# Analog.net
KiCad netlist of a schematic drawn in Altium Designer
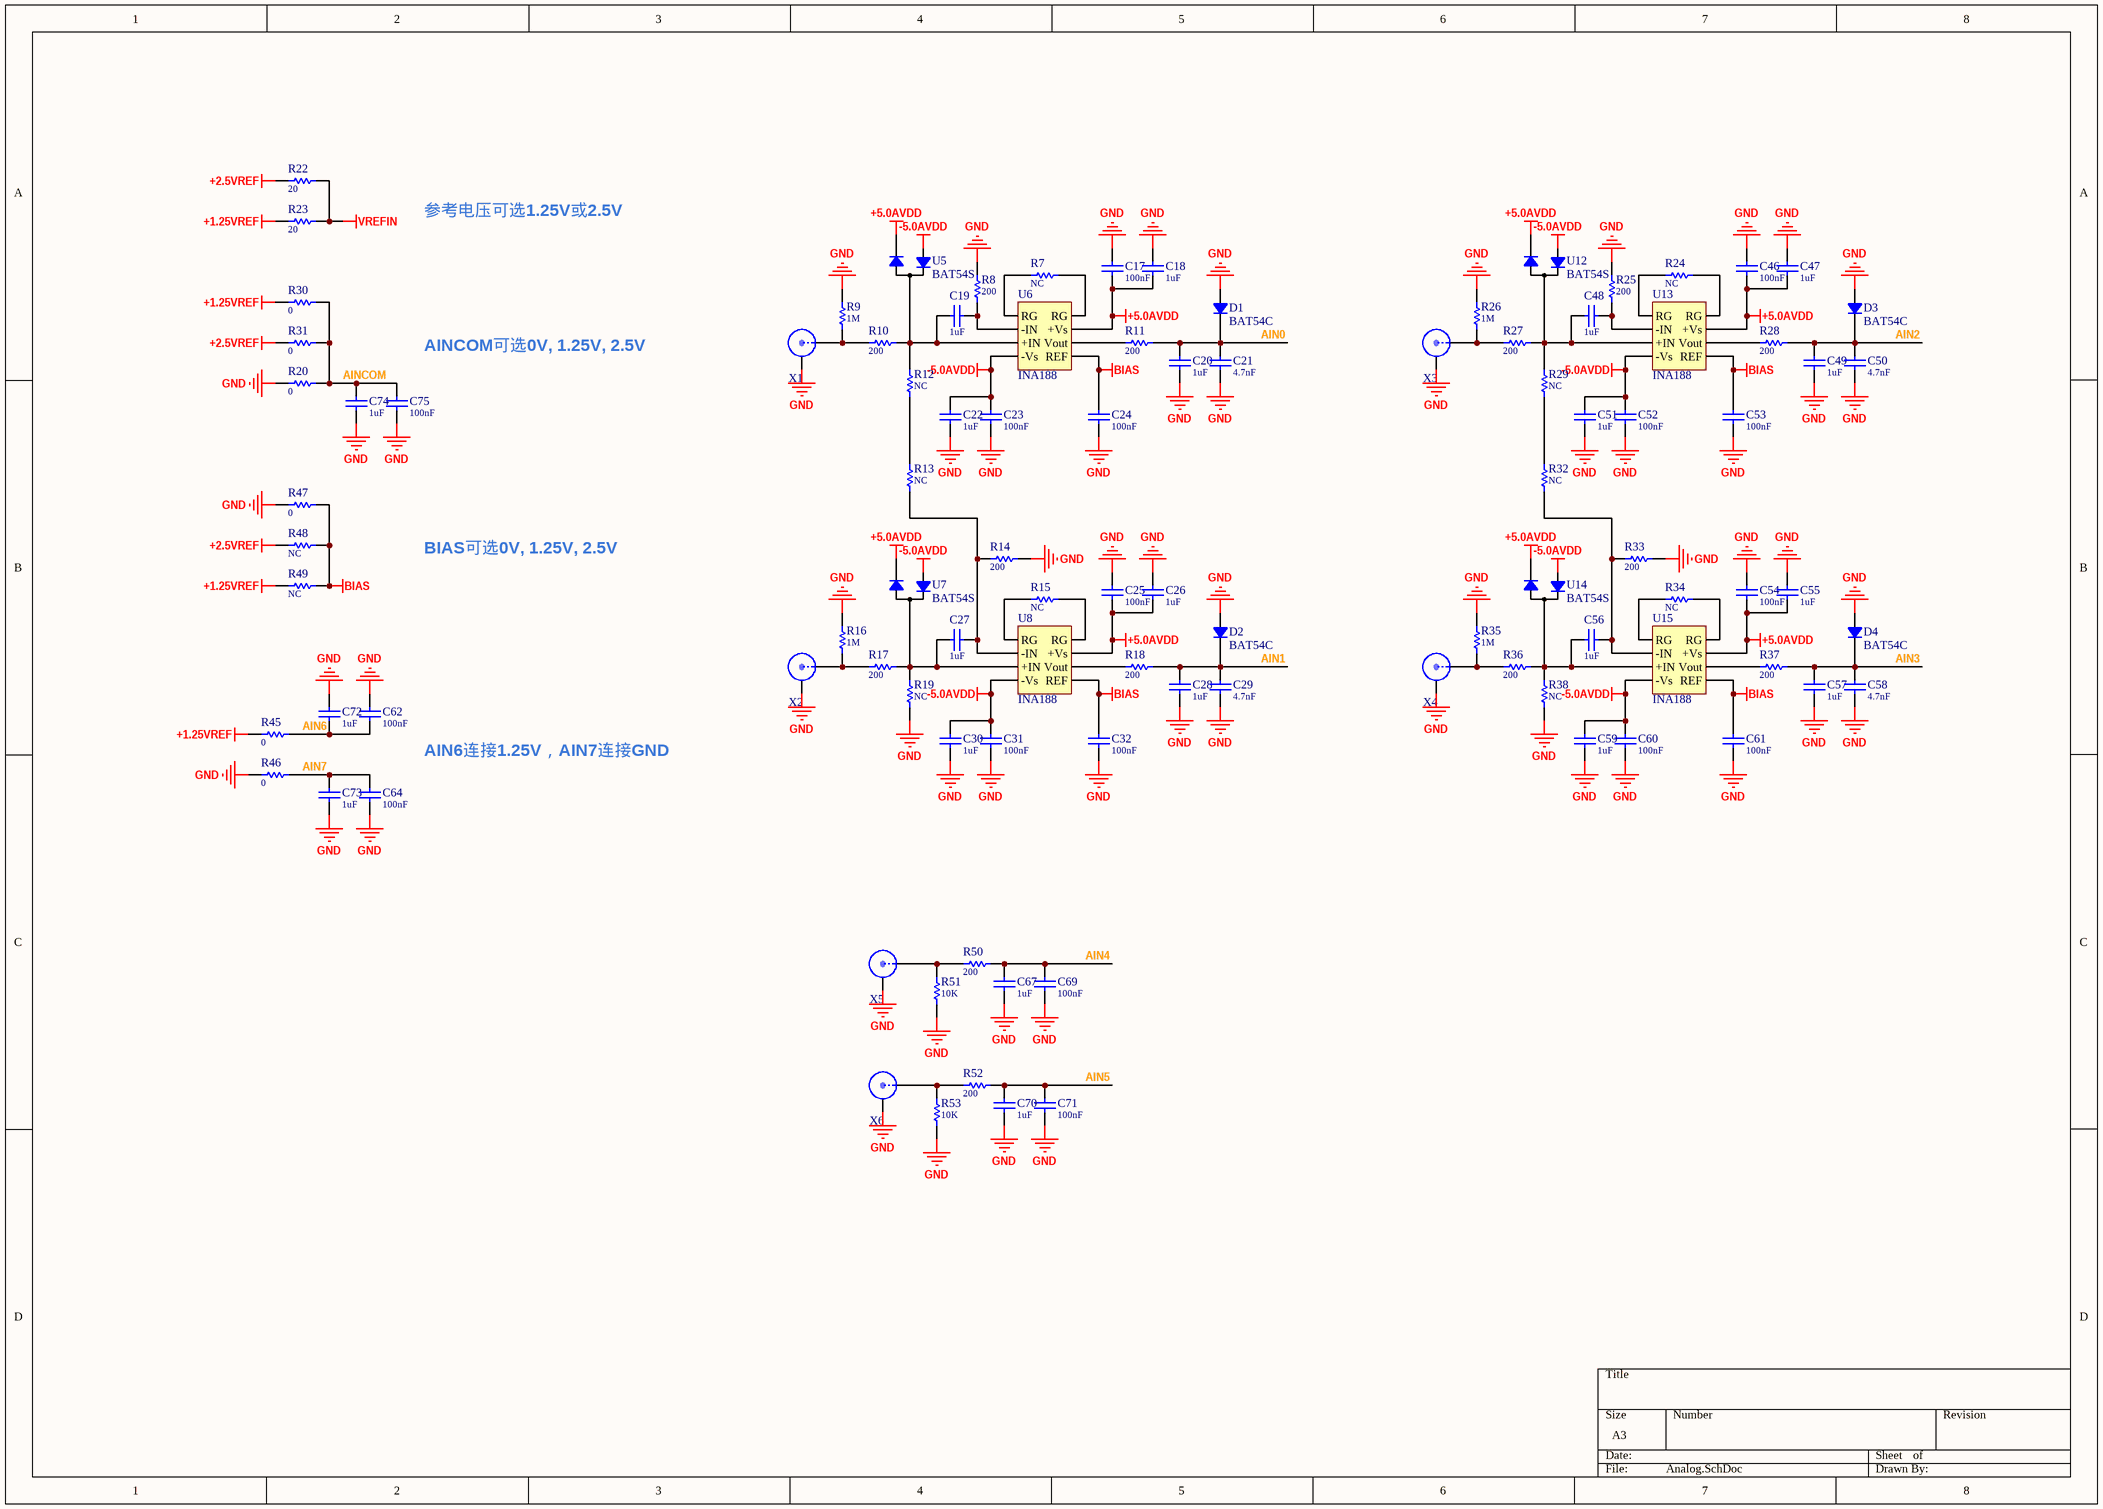
[diagram p0: Analog.SchDoc]

(export (version "E")
  (design (tool "Eeschema 10.0.6"))
  (components
    (comp (ref "C17")
      (value "100nF")
      (footprint "C0402-L")
      (description "贴片瓷片电容")
      (fields (field (name "Comment") "Cap-S"))
      (libsource (lib "xz_D") (part "Cap-S"))
    )
    (comp (ref "C18")
      (value "1uF")
      (footprint "C0603-L")
      (description "贴片瓷片电容")
      (fields (field (name "Comment") "Cap-S"))
      (libsource (lib "xz_D") (part "Cap-S"))
    )
    (comp (ref "C19")
      (value "1uF")
      (footprint "C0603-L")
      (description "贴片瓷片电容")
      (fields (field (name "Comment") "Cap-S"))
      (libsource (lib "xz_D") (part "Cap-S"))
    )
    (comp (ref "C20")
      (value "1uF")
      (footprint "C0603-L")
      (description "贴片瓷片电容")
      (fields (field (name "Comment") "Cap-S"))
      (libsource (lib "xz_D") (part "Cap-S"))
    )
    (comp (ref "C21")
      (value "4.7nF")
      (footprint "C0402-L")
      (description "贴片瓷片电容")
      (fields (field (name "Comment") "Cap-S"))
      (libsource (lib "xz_D") (part "Cap-S"))
    )
    (comp (ref "C22")
      (value "1uF")
      (footprint "C0603-L")
      (description "贴片瓷片电容")
      (fields (field (name "Comment") "Cap-S"))
      (libsource (lib "xz_D") (part "Cap-S"))
    )
    (comp (ref "C23")
      (value "100nF")
      (footprint "C0402-L")
      (description "贴片瓷片电容")
      (fields (field (name "Comment") "Cap-S"))
      (libsource (lib "xz_D") (part "Cap-S"))
    )
    (comp (ref "C24")
      (value "100nF")
      (footprint "C0402-L")
      (description "贴片瓷片电容")
      (fields (field (name "Comment") "Cap-S"))
      (libsource (lib "xz_D") (part "Cap-S"))
    )
    (comp (ref "C25")
      (value "100nF")
      (footprint "C0402-L")
      (description "贴片瓷片电容")
      (fields (field (name "Comment") "Cap-S"))
      (libsource (lib "xz_D") (part "Cap-S"))
    )
    (comp (ref "C26")
      (value "1uF")
      (footprint "C0603-L")
      (description "贴片瓷片电容")
      (fields (field (name "Comment") "Cap-S"))
      (libsource (lib "xz_D") (part "Cap-S"))
    )
    (comp (ref "C27")
      (value "1uF")
      (footprint "C0603-L")
      (description "贴片瓷片电容")
      (fields (field (name "Comment") "Cap-S"))
      (libsource (lib "xz_D") (part "Cap-S"))
    )
    (comp (ref "C28")
      (value "1uF")
      (footprint "C0603-L")
      (description "贴片瓷片电容")
      (fields (field (name "Comment") "Cap-S"))
      (libsource (lib "xz_D") (part "Cap-S"))
    )
    (comp (ref "C29")
      (value "4.7nF")
      (footprint "C0402-L")
      (description "贴片瓷片电容")
      (fields (field (name "Comment") "Cap-S"))
      (libsource (lib "xz_D") (part "Cap-S"))
    )
    (comp (ref "C30")
      (value "1uF")
      (footprint "C0603-L")
      (description "贴片瓷片电容")
      (fields (field (name "Comment") "Cap-S"))
      (libsource (lib "xz_D") (part "Cap-S"))
    )
    (comp (ref "C31")
      (value "100nF")
      (footprint "C0402-L")
      (description "贴片瓷片电容")
      (fields (field (name "Comment") "Cap-S"))
      (libsource (lib "xz_D") (part "Cap-S"))
    )
    (comp (ref "C32")
      (value "100nF")
      (footprint "C0402-L")
      (description "贴片瓷片电容")
      (fields (field (name "Comment") "Cap-S"))
      (libsource (lib "xz_D") (part "Cap-S"))
    )
    (comp (ref "C46")
      (value "100nF")
      (footprint "C0402-L")
      (description "贴片瓷片电容")
      (fields (field (name "Comment") "Cap-S"))
      (libsource (lib "xz_D") (part "Cap-S"))
    )
    (comp (ref "C47")
      (value "1uF")
      (footprint "C0603-L")
      (description "贴片瓷片电容")
      (fields (field (name "Comment") "Cap-S"))
      (libsource (lib "xz_D") (part "Cap-S"))
    )
    (comp (ref "C48")
      (value "1uF")
      (footprint "C0603-L")
      (description "贴片瓷片电容")
      (fields (field (name "Comment") "Cap-S"))
      (libsource (lib "xz_D") (part "Cap-S"))
    )
    (comp (ref "C49")
      (value "1uF")
      (footprint "C0603-L")
      (description "贴片瓷片电容")
      (fields (field (name "Comment") "Cap-S"))
      (libsource (lib "xz_D") (part "Cap-S"))
    )
    (comp (ref "C50")
      (value "4.7nF")
      (footprint "C0402-L")
      (description "贴片瓷片电容")
      (fields (field (name "Comment") "Cap-S"))
      (libsource (lib "xz_D") (part "Cap-S"))
    )
    (comp (ref "C51")
      (value "1uF")
      (footprint "C0603-L")
      (description "贴片瓷片电容")
      (fields (field (name "Comment") "Cap-S"))
      (libsource (lib "xz_D") (part "Cap-S"))
    )
    (comp (ref "C52")
      (value "100nF")
      (footprint "C0402-L")
      (description "贴片瓷片电容")
      (fields (field (name "Comment") "Cap-S"))
      (libsource (lib "xz_D") (part "Cap-S"))
    )
    (comp (ref "C53")
      (value "100nF")
      (footprint "C0402-L")
      (description "贴片瓷片电容")
      (fields (field (name "Comment") "Cap-S"))
      (libsource (lib "xz_D") (part "Cap-S"))
    )
    (comp (ref "C54")
      (value "100nF")
      (footprint "C0402-L")
      (description "贴片瓷片电容")
      (fields (field (name "Comment") "Cap-S"))
      (libsource (lib "xz_D") (part "Cap-S"))
    )
    (comp (ref "C55")
      (value "1uF")
      (footprint "C0603-L")
      (description "贴片瓷片电容")
      (fields (field (name "Comment") "Cap-S"))
      (libsource (lib "xz_D") (part "Cap-S"))
    )
    (comp (ref "C56")
      (value "1uF")
      (footprint "C0603-L")
      (description "贴片瓷片电容")
      (fields (field (name "Comment") "Cap-S"))
      (libsource (lib "xz_D") (part "Cap-S"))
    )
    (comp (ref "C57")
      (value "1uF")
      (footprint "C0603-L")
      (description "贴片瓷片电容")
      (fields (field (name "Comment") "Cap-S"))
      (libsource (lib "xz_D") (part "Cap-S"))
    )
    (comp (ref "C58")
      (value "4.7nF")
      (footprint "C0402-L")
      (description "贴片瓷片电容")
      (fields (field (name "Comment") "Cap-S"))
      (libsource (lib "xz_D") (part "Cap-S"))
    )
    (comp (ref "C59")
      (value "1uF")
      (footprint "C0603-L")
      (description "贴片瓷片电容")
      (fields (field (name "Comment") "Cap-S"))
      (libsource (lib "xz_D") (part "Cap-S"))
    )
    (comp (ref "C60")
      (value "100nF")
      (footprint "C0402-L")
      (description "贴片瓷片电容")
      (fields (field (name "Comment") "Cap-S"))
      (libsource (lib "xz_D") (part "Cap-S"))
    )
    (comp (ref "C61")
      (value "100nF")
      (footprint "C0402-L")
      (description "贴片瓷片电容")
      (fields (field (name "Comment") "Cap-S"))
      (libsource (lib "xz_D") (part "Cap-S"))
    )
    (comp (ref "C62")
      (value "100nF")
      (footprint "C0402-L")
      (description "贴片瓷片电容")
      (fields (field (name "Comment") "Cap-S"))
      (libsource (lib "xz_D") (part "Cap-S"))
    )
    (comp (ref "C64")
      (value "100nF")
      (footprint "C0402-L")
      (description "贴片瓷片电容")
      (fields (field (name "Comment") "Cap-S"))
      (libsource (lib "xz_D") (part "Cap-S"))
    )
    (comp (ref "C67")
      (value "1uF")
      (footprint "C0603-L")
      (description "贴片瓷片电容")
      (fields (field (name "Comment") "Cap-S"))
      (libsource (lib "xz_D") (part "Cap-S"))
    )
    (comp (ref "C69")
      (value "100nF")
      (footprint "C0402-L")
      (description "贴片瓷片电容")
      (fields (field (name "Comment") "Cap-S"))
      (libsource (lib "xz_D") (part "Cap-S"))
    )
    (comp (ref "C70")
      (value "1uF")
      (footprint "C0603-L")
      (description "贴片瓷片电容")
      (fields (field (name "Comment") "Cap-S"))
      (libsource (lib "xz_D") (part "Cap-S"))
    )
    (comp (ref "C71")
      (value "100nF")
      (footprint "C0402-L")
      (description "贴片瓷片电容")
      (fields (field (name "Comment") "Cap-S"))
      (libsource (lib "xz_D") (part "Cap-S"))
    )
    (comp (ref "C72")
      (value "1uF")
      (footprint "C0603-L")
      (description "贴片瓷片电容")
      (fields (field (name "Comment") "Cap-S"))
      (libsource (lib "xz_D") (part "Cap-S"))
    )
    (comp (ref "C73")
      (value "1uF")
      (footprint "C0603-L")
      (description "贴片瓷片电容")
      (fields (field (name "Comment") "Cap-S"))
      (libsource (lib "xz_D") (part "Cap-S"))
    )
    (comp (ref "C74")
      (value "1uF")
      (footprint "C0603-L")
      (description "贴片瓷片电容")
      (fields (field (name "Comment") "Cap-S"))
      (libsource (lib "xz_D") (part "Cap-S"))
    )
    (comp (ref "C75")
      (value "100nF")
      (footprint "C0402-L")
      (description "贴片瓷片电容")
      (fields (field (name "Comment") "Cap-S"))
      (libsource (lib "xz_D") (part "Cap-S"))
    )
    (comp (ref "D1") (value "BAT54C") (footprint "SOT-23-2") (libsource (lib "CommonUsed") (part "BAT54C")))
    (comp (ref "D2") (value "BAT54C") (footprint "SOT-23-2") (libsource (lib "CommonUsed") (part "BAT54C")))
    (comp (ref "D3") (value "BAT54C") (footprint "SOT-23-2") (libsource (lib "CommonUsed") (part "BAT54C")))
    (comp (ref "D4") (value "BAT54C") (footprint "SOT-23-2") (libsource (lib "CommonUsed") (part "BAT54C")))
    (comp (ref "R7")
      (value "NC")
      (footprint "R0603-L")
      (description "贴片电阻")
      (fields (field (name "Comment") "R"))
      (libsource (lib "xz_D") (part "Res"))
    )
    (comp (ref "R8")
      (value "200")
      (footprint "R0603-L")
      (description "贴片电阻")
      (fields (field (name "Comment") "R"))
      (libsource (lib "xz_D") (part "Res"))
    )
    (comp (ref "R9")
      (value "1M")
      (footprint "R0603-L")
      (description "贴片电阻")
      (fields (field (name "Comment") "R"))
      (libsource (lib "xz_D") (part "Res"))
    )
    (comp (ref "R10")
      (value "200")
      (footprint "R0603-L")
      (description "贴片电阻")
      (fields (field (name "Comment") "R"))
      (libsource (lib "xz_D") (part "Res"))
    )
    (comp (ref "R11")
      (value "200")
      (footprint "R0603-L")
      (description "贴片电阻")
      (fields (field (name "Comment") "R"))
      (libsource (lib "xz_D") (part "Res"))
    )
    (comp (ref "R12")
      (value "NC")
      (footprint "R0603-L")
      (description "贴片电阻")
      (fields (field (name "Comment") "R"))
      (libsource (lib "xz_D") (part "Res"))
    )
    (comp (ref "R13")
      (value "NC")
      (footprint "R0603-L")
      (description "贴片电阻")
      (fields (field (name "Comment") "R"))
      (libsource (lib "xz_D") (part "Res"))
    )
    (comp (ref "R14")
      (value "200")
      (footprint "R0603-L")
      (description "贴片电阻")
      (fields (field (name "Comment") "R"))
      (libsource (lib "xz_D") (part "Res"))
    )
    (comp (ref "R15")
      (value "NC")
      (footprint "R0603-L")
      (description "贴片电阻")
      (fields (field (name "Comment") "R"))
      (libsource (lib "xz_D") (part "Res"))
    )
    (comp (ref "R16")
      (value "1M")
      (footprint "R0603-L")
      (description "贴片电阻")
      (fields (field (name "Comment") "R"))
      (libsource (lib "xz_D") (part "Res"))
    )
    (comp (ref "R17")
      (value "200")
      (footprint "R0603-L")
      (description "贴片电阻")
      (fields (field (name "Comment") "R"))
      (libsource (lib "xz_D") (part "Res"))
    )
    (comp (ref "R18")
      (value "200")
      (footprint "R0603-L")
      (description "贴片电阻")
      (fields (field (name "Comment") "R"))
      (libsource (lib "xz_D") (part "Res"))
    )
    (comp (ref "R19")
      (value "NC")
      (footprint "R0603-L")
      (description "贴片电阻")
      (fields (field (name "Comment") "R"))
      (libsource (lib "xz_D") (part "Res"))
    )
    (comp (ref "R20")
      (value "0")
      (footprint "R0603-L")
      (description "贴片电阻")
      (fields (field (name "Comment") "R"))
      (libsource (lib "xz_D") (part "Res"))
    )
    (comp (ref "R22")
      (value "20")
      (footprint "R0603-L")
      (description "贴片电阻")
      (fields (field (name "Comment") "R"))
      (libsource (lib "xz_D") (part "Res"))
    )
    (comp (ref "R23")
      (value "20")
      (footprint "R0603-L")
      (description "贴片电阻")
      (fields (field (name "Comment") "R"))
      (libsource (lib "xz_D") (part "Res"))
    )
    (comp (ref "R24")
      (value "NC")
      (footprint "R0603-L")
      (description "贴片电阻")
      (fields (field (name "Comment") "R"))
      (libsource (lib "xz_D") (part "Res"))
    )
    (comp (ref "R25")
      (value "200")
      (footprint "R0603-L")
      (description "贴片电阻")
      (fields (field (name "Comment") "R"))
      (libsource (lib "xz_D") (part "Res"))
    )
    (comp (ref "R26")
      (value "1M")
      (footprint "R0603-L")
      (description "贴片电阻")
      (fields (field (name "Comment") "R"))
      (libsource (lib "xz_D") (part "Res"))
    )
    (comp (ref "R27")
      (value "200")
      (footprint "R0603-L")
      (description "贴片电阻")
      (fields (field (name "Comment") "R"))
      (libsource (lib "xz_D") (part "Res"))
    )
    (comp (ref "R28")
      (value "200")
      (footprint "R0603-L")
      (description "贴片电阻")
      (fields (field (name "Comment") "R"))
      (libsource (lib "xz_D") (part "Res"))
    )
    (comp (ref "R29")
      (value "NC")
      (footprint "R0603-L")
      (description "贴片电阻")
      (fields (field (name "Comment") "R"))
      (libsource (lib "xz_D") (part "Res"))
    )
    (comp (ref "R30")
      (value "0")
      (footprint "R0603-L")
      (description "贴片电阻")
      (fields (field (name "Comment") "R"))
      (libsource (lib "xz_D") (part "Res"))
    )
    (comp (ref "R31")
      (value "0")
      (footprint "R0603-L")
      (description "贴片电阻")
      (fields (field (name "Comment") "R"))
      (libsource (lib "xz_D") (part "Res"))
    )
    (comp (ref "R32")
      (value "NC")
      (footprint "R0603-L")
      (description "贴片电阻")
      (fields (field (name "Comment") "R"))
      (libsource (lib "xz_D") (part "Res"))
    )
    (comp (ref "R33")
      (value "200")
      (footprint "R0603-L")
      (description "贴片电阻")
      (fields (field (name "Comment") "R"))
      (libsource (lib "xz_D") (part "Res"))
    )
    (comp (ref "R34")
      (value "NC")
      (footprint "R0603-L")
      (description "贴片电阻")
      (fields (field (name "Comment") "R"))
      (libsource (lib "xz_D") (part "Res"))
    )
    (comp (ref "R35")
      (value "1M")
      (footprint "R0603-L")
      (description "贴片电阻")
      (fields (field (name "Comment") "R"))
      (libsource (lib "xz_D") (part "Res"))
    )
    (comp (ref "R36")
      (value "200")
      (footprint "R0603-L")
      (description "贴片电阻")
      (fields (field (name "Comment") "R"))
      (libsource (lib "xz_D") (part "Res"))
    )
    (comp (ref "R37")
      (value "200")
      (footprint "R0603-L")
      (description "贴片电阻")
      (fields (field (name "Comment") "R"))
      (libsource (lib "xz_D") (part "Res"))
    )
    (comp (ref "R38")
      (value "NC")
      (footprint "R0603-L")
      (description "贴片电阻")
      (fields (field (name "Comment") "R"))
      (libsource (lib "xz_D") (part "Res"))
    )
    (comp (ref "R45")
      (value "0")
      (footprint "R0603-L")
      (description "贴片电阻")
      (fields (field (name "Comment") "R"))
      (libsource (lib "xz_D") (part "Res"))
    )
    (comp (ref "R46")
      (value "0")
      (footprint "R0603-L")
      (description "贴片电阻")
      (fields (field (name "Comment") "R"))
      (libsource (lib "xz_D") (part "Res"))
    )
    (comp (ref "R47")
      (value "0")
      (footprint "R0603-L")
      (description "贴片电阻")
      (fields (field (name "Comment") "R"))
      (libsource (lib "xz_D") (part "Res"))
    )
    (comp (ref "R48")
      (value "NC")
      (footprint "R0603-L")
      (description "贴片电阻")
      (fields (field (name "Comment") "R"))
      (libsource (lib "xz_D") (part "Res"))
    )
    (comp (ref "R49")
      (value "NC")
      (footprint "R0603-L")
      (description "贴片电阻")
      (fields (field (name "Comment") "R"))
      (libsource (lib "xz_D") (part "Res"))
    )
    (comp (ref "R50")
      (value "200")
      (footprint "R0603-L")
      (description "贴片电阻")
      (fields (field (name "Comment") "R"))
      (libsource (lib "xz_D") (part "Res"))
    )
    (comp (ref "R51")
      (value "10K")
      (footprint "R0603-L")
      (description "贴片电阻")
      (fields (field (name "Comment") "R"))
      (libsource (lib "xz_D") (part "Res"))
    )
    (comp (ref "R52")
      (value "200")
      (footprint "R0603-L")
      (description "贴片电阻")
      (fields (field (name "Comment") "R"))
      (libsource (lib "xz_D") (part "Res"))
    )
    (comp (ref "R53")
      (value "10K")
      (footprint "R0603-L")
      (description "贴片电阻")
      (fields (field (name "Comment") "R"))
      (libsource (lib "xz_D") (part "Res"))
    )
    (comp (ref "U5") (value "BAT54S") (footprint "SOT-23-3") (libsource (lib "CommonUsed") (part "BAT54S")))
    (comp (ref "U6") (value "INA188") (footprint "SOP-8") (libsource (lib "CommonUsed") (part "InAmp")))
    (comp (ref "U7") (value "BAT54S") (footprint "SOT-23-3") (libsource (lib "CommonUsed") (part "BAT54S")))
    (comp (ref "U8") (value "INA188") (footprint "SOP-8") (libsource (lib "CommonUsed") (part "InAmp")))
    (comp (ref "U12") (value "BAT54S") (footprint "SOT-23-3") (libsource (lib "CommonUsed") (part "BAT54S")))
    (comp (ref "U13") (value "INA188") (footprint "SOP-8") (libsource (lib "CommonUsed") (part "InAmp")))
    (comp (ref "U14") (value "BAT54S") (footprint "SOT-23-3") (libsource (lib "CommonUsed") (part "BAT54S")))
    (comp (ref "U15") (value "INA188") (footprint "SOP-8") (libsource (lib "CommonUsed") (part "InAmp")))
    (comp (ref "X1") (value "SMA") (footprint "SMA_ANGLE") (libsource (lib "xz_C") (part "SMA")))
    (comp (ref "X2") (value "SMA") (footprint "SMA_ANGLE") (libsource (lib "xz_C") (part "SMA")))
    (comp (ref "X3") (value "SMA") (footprint "SMA_ANGLE") (libsource (lib "xz_C") (part "SMA")))
    (comp (ref "X4") (value "SMA") (footprint "SMA_ANGLE") (libsource (lib "xz_C") (part "SMA")))
    (comp (ref "X5") (value "SMA") (footprint "SMA_ANGLE") (libsource (lib "xz_C") (part "SMA")))
    (comp (ref "X6") (value "SMA") (footprint "SMA_ANGLE") (libsource (lib "xz_C") (part "SMA")))
  )
  (nets
    (net (code "1") (name "+1.25VREF") (class "Default")
      (node (ref "R23") (pin "1") (pinfunction "1_1") (pintype "passive"))
      (node (ref "R30") (pin "2") (pinfunction "2_2") (pintype "passive"))
      (node (ref "R45") (pin "2") (pinfunction "2_2") (pintype "passive"))
      (node (ref "R49") (pin "2") (pinfunction "2_2") (pintype "passive"))
    )
    (net (code "2") (name "+2.5VREF") (class "Default")
      (node (ref "R22") (pin "1") (pinfunction "1_1") (pintype "passive"))
      (node (ref "R31") (pin "2") (pinfunction "2_2") (pintype "passive"))
      (node (ref "R48") (pin "2") (pinfunction "2_2") (pintype "passive"))
    )
    (net (code "3") (name "+5.0AVDD") (class "Default")
      (node (ref "C17") (pin "2") (pinfunction "2_2") (pintype "passive"))
      (node (ref "C18") (pin "2") (pinfunction "2_2") (pintype "passive"))
      (node (ref "C25") (pin "2") (pinfunction "2_2") (pintype "passive"))
      (node (ref "C26") (pin "2") (pinfunction "2_2") (pintype "passive"))
      (node (ref "C46") (pin "2") (pinfunction "2_2") (pintype "passive"))
      (node (ref "C47") (pin "2") (pinfunction "2_2") (pintype "passive"))
      (node (ref "C54") (pin "2") (pinfunction "2_2") (pintype "passive"))
      (node (ref "C55") (pin "2") (pinfunction "2_2") (pintype "passive"))
      (node (ref "U12") (pin "3") (pinfunction "3_3") (pintype "passive"))
      (node (ref "U13") (pin "7") (pinfunction "+Vs_7") (pintype "passive"))
      (node (ref "U14") (pin "3") (pinfunction "3_3") (pintype "passive"))
      (node (ref "U15") (pin "7") (pinfunction "+Vs_7") (pintype "passive"))
      (node (ref "U5") (pin "3") (pinfunction "3_3") (pintype "passive"))
      (node (ref "U6") (pin "7") (pinfunction "+Vs_7") (pintype "passive"))
      (node (ref "U7") (pin "3") (pinfunction "3_3") (pintype "passive"))
      (node (ref "U8") (pin "7") (pinfunction "+Vs_7") (pintype "passive"))
    )
    (net (code "4") (name "-5.0AVDD") (class "Default")
      (node (ref "C22") (pin "1") (pinfunction "1_1") (pintype "passive"))
      (node (ref "C23") (pin "2") (pinfunction "2_2") (pintype "passive"))
      (node (ref "C30") (pin "1") (pinfunction "1_1") (pintype "passive"))
      (node (ref "C31") (pin "2") (pinfunction "2_2") (pintype "passive"))
      (node (ref "C51") (pin "1") (pinfunction "1_1") (pintype "passive"))
      (node (ref "C52") (pin "2") (pinfunction "2_2") (pintype "passive"))
      (node (ref "C59") (pin "1") (pinfunction "1_1") (pintype "passive"))
      (node (ref "C60") (pin "2") (pinfunction "2_2") (pintype "passive"))
      (node (ref "U12") (pin "1") (pinfunction "1_1") (pintype "passive"))
      (node (ref "U13") (pin "4") (pinfunction "-Vs_4") (pintype "passive"))
      (node (ref "U14") (pin "1") (pinfunction "1_1") (pintype "passive"))
      (node (ref "U15") (pin "4") (pinfunction "-Vs_4") (pintype "passive"))
      (node (ref "U5") (pin "1") (pinfunction "1_1") (pintype "passive"))
      (node (ref "U6") (pin "4") (pinfunction "-Vs_4") (pintype "passive"))
      (node (ref "U7") (pin "1") (pinfunction "1_1") (pintype "passive"))
      (node (ref "U8") (pin "4") (pinfunction "-Vs_4") (pintype "passive"))
    )
    (net (code "5") (name "/AIN0") (class "Default")
      (node (ref "C20") (pin "1") (pinfunction "1_1") (pintype "passive"))
      (node (ref "C21") (pin "1") (pinfunction "1_1") (pintype "passive"))
      (node (ref "D1") (pin "2") (pinfunction "2_2") (pintype "passive"))
      (node (ref "R11") (pin "1") (pinfunction "1_1") (pintype "passive"))
    )
    (net (code "6") (name "/AIN1") (class "Default")
      (node (ref "C28") (pin "1") (pinfunction "1_1") (pintype "passive"))
      (node (ref "C29") (pin "1") (pinfunction "1_1") (pintype "passive"))
      (node (ref "D2") (pin "2") (pinfunction "2_2") (pintype "passive"))
      (node (ref "R18") (pin "1") (pinfunction "1_1") (pintype "passive"))
    )
    (net (code "7") (name "/AIN2") (class "Default")
      (node (ref "C49") (pin "1") (pinfunction "1_1") (pintype "passive"))
      (node (ref "C50") (pin "1") (pinfunction "1_1") (pintype "passive"))
      (node (ref "D3") (pin "2") (pinfunction "2_2") (pintype "passive"))
      (node (ref "R28") (pin "1") (pinfunction "1_1") (pintype "passive"))
    )
    (net (code "8") (name "/AIN3") (class "Default")
      (node (ref "C57") (pin "1") (pinfunction "1_1") (pintype "passive"))
      (node (ref "C58") (pin "1") (pinfunction "1_1") (pintype "passive"))
      (node (ref "D4") (pin "2") (pinfunction "2_2") (pintype "passive"))
      (node (ref "R37") (pin "1") (pinfunction "1_1") (pintype "passive"))
    )
    (net (code "9") (name "/AIN4") (class "Default")
      (node (ref "C67") (pin "2") (pinfunction "2_2") (pintype "passive"))
      (node (ref "C69") (pin "2") (pinfunction "2_2") (pintype "passive"))
      (node (ref "R50") (pin "1") (pinfunction "1_1") (pintype "passive"))
    )
    (net (code "10") (name "/AIN5") (class "Default")
      (node (ref "C70") (pin "2") (pinfunction "2_2") (pintype "passive"))
      (node (ref "C71") (pin "2") (pinfunction "2_2") (pintype "passive"))
      (node (ref "R52") (pin "1") (pinfunction "1_1") (pintype "passive"))
    )
    (net (code "11") (name "/AIN6") (class "Default")
      (node (ref "C62") (pin "2") (pinfunction "2_2") (pintype "passive"))
      (node (ref "C72") (pin "1") (pinfunction "1_1") (pintype "passive"))
      (node (ref "R45") (pin "1") (pinfunction "1_1") (pintype "passive"))
    )
    (net (code "12") (name "/AIN7") (class "Default")
      (node (ref "C64") (pin "1") (pinfunction "1_1") (pintype "passive"))
      (node (ref "C73") (pin "1") (pinfunction "1_1") (pintype "passive"))
      (node (ref "R46") (pin "1") (pinfunction "1_1") (pintype "passive"))
    )
    (net (code "13") (name "/AINCOM") (class "Default")
      (node (ref "C74") (pin "1") (pinfunction "1_1") (pintype "passive"))
      (node (ref "C75") (pin "1") (pinfunction "1_1") (pintype "passive"))
      (node (ref "R20") (pin "1") (pinfunction "1_1") (pintype "passive"))
      (node (ref "R30") (pin "1") (pinfunction "1_1") (pintype "passive"))
      (node (ref "R31") (pin "1") (pinfunction "1_1") (pintype "passive"))
    )
    (net (code "14") (name "BIAS") (class "Default")
      (node (ref "C24") (pin "2") (pinfunction "2_2") (pintype "passive"))
      (node (ref "C32") (pin "2") (pinfunction "2_2") (pintype "passive"))
      (node (ref "C53") (pin "2") (pinfunction "2_2") (pintype "passive"))
      (node (ref "C61") (pin "2") (pinfunction "2_2") (pintype "passive"))
      (node (ref "R47") (pin "1") (pinfunction "1_1") (pintype "passive"))
      (node (ref "R48") (pin "1") (pinfunction "1_1") (pintype "passive"))
      (node (ref "R49") (pin "1") (pinfunction "1_1") (pintype "passive"))
      (node (ref "U13") (pin "5") (pinfunction "REF_5") (pintype "passive"))
      (node (ref "U15") (pin "5") (pinfunction "REF_5") (pintype "passive"))
      (node (ref "U6") (pin "5") (pinfunction "REF_5") (pintype "passive"))
      (node (ref "U8") (pin "5") (pinfunction "REF_5") (pintype "passive"))
    )
    (net (code "15") (name "GND") (class "Default")
      (node (ref "C17") (pin "1") (pinfunction "1_1") (pintype "passive"))
      (node (ref "C18") (pin "1") (pinfunction "1_1") (pintype "passive"))
      (node (ref "C20") (pin "2") (pinfunction "2_2") (pintype "passive"))
      (node (ref "C21") (pin "2") (pinfunction "2_2") (pintype "passive"))
      (node (ref "C22") (pin "2") (pinfunction "2_2") (pintype "passive"))
      (node (ref "C23") (pin "1") (pinfunction "1_1") (pintype "passive"))
      (node (ref "C24") (pin "1") (pinfunction "1_1") (pintype "passive"))
      (node (ref "C25") (pin "1") (pinfunction "1_1") (pintype "passive"))
      (node (ref "C26") (pin "1") (pinfunction "1_1") (pintype "passive"))
      (node (ref "C28") (pin "2") (pinfunction "2_2") (pintype "passive"))
      (node (ref "C29") (pin "2") (pinfunction "2_2") (pintype "passive"))
      (node (ref "C30") (pin "2") (pinfunction "2_2") (pintype "passive"))
      (node (ref "C31") (pin "1") (pinfunction "1_1") (pintype "passive"))
      (node (ref "C32") (pin "1") (pinfunction "1_1") (pintype "passive"))
      (node (ref "C46") (pin "1") (pinfunction "1_1") (pintype "passive"))
      (node (ref "C47") (pin "1") (pinfunction "1_1") (pintype "passive"))
      (node (ref "C49") (pin "2") (pinfunction "2_2") (pintype "passive"))
      (node (ref "C50") (pin "2") (pinfunction "2_2") (pintype "passive"))
      (node (ref "C51") (pin "2") (pinfunction "2_2") (pintype "passive"))
      (node (ref "C52") (pin "1") (pinfunction "1_1") (pintype "passive"))
      (node (ref "C53") (pin "1") (pinfunction "1_1") (pintype "passive"))
      (node (ref "C54") (pin "1") (pinfunction "1_1") (pintype "passive"))
      (node (ref "C55") (pin "1") (pinfunction "1_1") (pintype "passive"))
      (node (ref "C57") (pin "2") (pinfunction "2_2") (pintype "passive"))
      (node (ref "C58") (pin "2") (pinfunction "2_2") (pintype "passive"))
      (node (ref "C59") (pin "2") (pinfunction "2_2") (pintype "passive"))
      (node (ref "C60") (pin "1") (pinfunction "1_1") (pintype "passive"))
      (node (ref "C61") (pin "1") (pinfunction "1_1") (pintype "passive"))
      (node (ref "C62") (pin "1") (pinfunction "1_1") (pintype "passive"))
      (node (ref "C64") (pin "2") (pinfunction "2_2") (pintype "passive"))
      (node (ref "C67") (pin "1") (pinfunction "1_1") (pintype "passive"))
      (node (ref "C69") (pin "1") (pinfunction "1_1") (pintype "passive"))
      (node (ref "C70") (pin "1") (pinfunction "1_1") (pintype "passive"))
      (node (ref "C71") (pin "1") (pinfunction "1_1") (pintype "passive"))
      (node (ref "C72") (pin "2") (pinfunction "2_2") (pintype "passive"))
      (node (ref "C73") (pin "2") (pinfunction "2_2") (pintype "passive"))
      (node (ref "C74") (pin "2") (pinfunction "2_2") (pintype "passive"))
      (node (ref "C75") (pin "2") (pinfunction "2_2") (pintype "passive"))
      (node (ref "D1") (pin "1") (pinfunction "1_1") (pintype "passive"))
      (node (ref "D2") (pin "1") (pinfunction "1_1") (pintype "passive"))
      (node (ref "D3") (pin "1") (pinfunction "1_1") (pintype "passive"))
      (node (ref "D4") (pin "1") (pinfunction "1_1") (pintype "passive"))
      (node (ref "R14") (pin "1") (pinfunction "1_1") (pintype "passive"))
      (node (ref "R16") (pin "1") (pinfunction "1_1") (pintype "passive"))
      (node (ref "R19") (pin "1") (pinfunction "1_1") (pintype "passive"))
      (node (ref "R20") (pin "2") (pinfunction "2_2") (pintype "passive"))
      (node (ref "R25") (pin "2") (pinfunction "2_2") (pintype "passive"))
      (node (ref "R26") (pin "1") (pinfunction "1_1") (pintype "passive"))
      (node (ref "R33") (pin "1") (pinfunction "1_1") (pintype "passive"))
      (node (ref "R35") (pin "1") (pinfunction "1_1") (pintype "passive"))
      (node (ref "R38") (pin "1") (pinfunction "1_1") (pintype "passive"))
      (node (ref "R46") (pin "2") (pinfunction "2_2") (pintype "passive"))
      (node (ref "R47") (pin "2") (pinfunction "2_2") (pintype "passive"))
      (node (ref "R51") (pin "2") (pinfunction "2_2") (pintype "passive"))
      (node (ref "R53") (pin "2") (pinfunction "2_2") (pintype "passive"))
      (node (ref "R8") (pin "2") (pinfunction "2_2") (pintype "passive"))
      (node (ref "R9") (pin "1") (pinfunction "1_1") (pintype "passive"))
      (node (ref "X1") (pin "2") (pinfunction "2_2") (pintype "passive"))
      (node (ref "X2") (pin "2") (pinfunction "2_2") (pintype "passive"))
      (node (ref "X3") (pin "2") (pinfunction "2_2") (pintype "passive"))
      (node (ref "X4") (pin "2") (pinfunction "2_2") (pintype "passive"))
      (node (ref "X5") (pin "2") (pinfunction "2_2") (pintype "passive"))
      (node (ref "X6") (pin "2") (pinfunction "2_2") (pintype "passive"))
    )
    (net (code "16") (name "Net-(R7-Pad1)") (class "Default")
      (node (ref "R7") (pin "1") (pinfunction "1_1") (pintype "passive"))
      (node (ref "U6") (pin "8") (pinfunction "RG_8") (pintype "passive"))
    )
    (net (code "17") (name "Net-(R7-Pad2)") (class "Default")
      (node (ref "R7") (pin "2") (pinfunction "2_2") (pintype "passive"))
      (node (ref "U6") (pin "1") (pinfunction "RG_1") (pintype "passive"))
    )
    (net (code "18") (name "Net-(R10-Pad2)") (class "Default")
      (node (ref "R10") (pin "2") (pinfunction "2_2") (pintype "passive"))
      (node (ref "R9") (pin "2") (pinfunction "2_2") (pintype "passive"))
      (node (ref "X1") (pin "1") (pinfunction "1_1") (pintype "passive"))
    )
    (net (code "19") (name "Net-(R12-Pad2)") (class "Default")
      (node (ref "R12") (pin "2") (pinfunction "2_2") (pintype "passive"))
      (node (ref "R13") (pin "1") (pinfunction "1_1") (pintype "passive"))
    )
    (net (code "20") (name "Net-(R15-Pad1)") (class "Default")
      (node (ref "R15") (pin "1") (pinfunction "1_1") (pintype "passive"))
      (node (ref "U8") (pin "8") (pinfunction "RG_8") (pintype "passive"))
    )
    (net (code "21") (name "Net-(R15-Pad2)") (class "Default")
      (node (ref "R15") (pin "2") (pinfunction "2_2") (pintype "passive"))
      (node (ref "U8") (pin "1") (pinfunction "RG_1") (pintype "passive"))
    )
    (net (code "22") (name "Net-(R16-Pad2)") (class "Default")
      (node (ref "R16") (pin "2") (pinfunction "2_2") (pintype "passive"))
      (node (ref "R17") (pin "2") (pinfunction "2_2") (pintype "passive"))
      (node (ref "X2") (pin "1") (pinfunction "1_1") (pintype "passive"))
    )
    (net (code "23") (name "Net-(R24-Pad1)") (class "Default")
      (node (ref "R24") (pin "1") (pinfunction "1_1") (pintype "passive"))
      (node (ref "U13") (pin "8") (pinfunction "RG_8") (pintype "passive"))
    )
    (net (code "24") (name "Net-(R24-Pad2)") (class "Default")
      (node (ref "R24") (pin "2") (pinfunction "2_2") (pintype "passive"))
      (node (ref "U13") (pin "1") (pinfunction "RG_1") (pintype "passive"))
    )
    (net (code "25") (name "Net-(R26-Pad2)") (class "Default")
      (node (ref "R26") (pin "2") (pinfunction "2_2") (pintype "passive"))
      (node (ref "R27") (pin "2") (pinfunction "2_2") (pintype "passive"))
      (node (ref "X3") (pin "1") (pinfunction "1_1") (pintype "passive"))
    )
    (net (code "26") (name "Net-(R29-Pad2)") (class "Default")
      (node (ref "R29") (pin "2") (pinfunction "2_2") (pintype "passive"))
      (node (ref "R32") (pin "1") (pinfunction "1_1") (pintype "passive"))
    )
    (net (code "27") (name "Net-(R34-Pad1)") (class "Default")
      (node (ref "R34") (pin "1") (pinfunction "1_1") (pintype "passive"))
      (node (ref "U15") (pin "8") (pinfunction "RG_8") (pintype "passive"))
    )
    (net (code "28") (name "Net-(R34-Pad2)") (class "Default")
      (node (ref "R34") (pin "2") (pinfunction "2_2") (pintype "passive"))
      (node (ref "U15") (pin "1") (pinfunction "RG_1") (pintype "passive"))
    )
    (net (code "29") (name "Net-(R35-Pad2)") (class "Default")
      (node (ref "R35") (pin "2") (pinfunction "2_2") (pintype "passive"))
      (node (ref "R36") (pin "2") (pinfunction "2_2") (pintype "passive"))
      (node (ref "X4") (pin "1") (pinfunction "1_1") (pintype "passive"))
    )
    (net (code "30") (name "Net-(R50-Pad2)") (class "Default")
      (node (ref "R50") (pin "2") (pinfunction "2_2") (pintype "passive"))
      (node (ref "R51") (pin "1") (pinfunction "1_1") (pintype "passive"))
      (node (ref "X5") (pin "1") (pinfunction "1_1") (pintype "passive"))
    )
    (net (code "31") (name "Net-(R52-Pad2)") (class "Default")
      (node (ref "R52") (pin "2") (pinfunction "2_2") (pintype "passive"))
      (node (ref "R53") (pin "1") (pinfunction "1_1") (pintype "passive"))
      (node (ref "X6") (pin "1") (pinfunction "1_1") (pintype "passive"))
    )
    (net (code "32") (name "Net-(U6-+IN)") (class "Default")
      (node (ref "C19") (pin "2") (pinfunction "2_2") (pintype "passive"))
      (node (ref "R10") (pin "1") (pinfunction "1_1") (pintype "passive"))
      (node (ref "R12") (pin "1") (pinfunction "1_1") (pintype "passive"))
      (node (ref "U5") (pin "2") (pinfunction "2_2") (pintype "passive"))
      (node (ref "U6") (pin "3") (pinfunction "+IN_3") (pintype "passive"))
    )
    (net (code "33") (name "Net-(U6--IN)") (class "Default")
      (node (ref "C19") (pin "1") (pinfunction "1_1") (pintype "passive"))
      (node (ref "R8") (pin "1") (pinfunction "1_1") (pintype "passive"))
      (node (ref "U6") (pin "2") (pinfunction "-IN_2") (pintype "passive"))
    )
    (net (code "34") (name "Net-(U6-Vout)") (class "Default")
      (node (ref "R11") (pin "2") (pinfunction "2_2") (pintype "passive"))
      (node (ref "U6") (pin "6") (pinfunction "Vout_6") (pintype "passive"))
    )
    (net (code "35") (name "Net-(U8-+IN)") (class "Default")
      (node (ref "C27") (pin "2") (pinfunction "2_2") (pintype "passive"))
      (node (ref "R17") (pin "1") (pinfunction "1_1") (pintype "passive"))
      (node (ref "R19") (pin "2") (pinfunction "2_2") (pintype "passive"))
      (node (ref "U7") (pin "2") (pinfunction "2_2") (pintype "passive"))
      (node (ref "U8") (pin "3") (pinfunction "+IN_3") (pintype "passive"))
    )
    (net (code "36") (name "Net-(U8--IN)") (class "Default")
      (node (ref "C27") (pin "1") (pinfunction "1_1") (pintype "passive"))
      (node (ref "R13") (pin "2") (pinfunction "2_2") (pintype "passive"))
      (node (ref "R14") (pin "2") (pinfunction "2_2") (pintype "passive"))
      (node (ref "U8") (pin "2") (pinfunction "-IN_2") (pintype "passive"))
    )
    (net (code "37") (name "Net-(U8-Vout)") (class "Default")
      (node (ref "R18") (pin "2") (pinfunction "2_2") (pintype "passive"))
      (node (ref "U8") (pin "6") (pinfunction "Vout_6") (pintype "passive"))
    )
    (net (code "38") (name "Net-(U13-+IN)") (class "Default")
      (node (ref "C48") (pin "2") (pinfunction "2_2") (pintype "passive"))
      (node (ref "R27") (pin "1") (pinfunction "1_1") (pintype "passive"))
      (node (ref "R29") (pin "1") (pinfunction "1_1") (pintype "passive"))
      (node (ref "U12") (pin "2") (pinfunction "2_2") (pintype "passive"))
      (node (ref "U13") (pin "3") (pinfunction "+IN_3") (pintype "passive"))
    )
    (net (code "39") (name "Net-(U13--IN)") (class "Default")
      (node (ref "C48") (pin "1") (pinfunction "1_1") (pintype "passive"))
      (node (ref "R25") (pin "1") (pinfunction "1_1") (pintype "passive"))
      (node (ref "U13") (pin "2") (pinfunction "-IN_2") (pintype "passive"))
    )
    (net (code "40") (name "Net-(U13-Vout)") (class "Default")
      (node (ref "R28") (pin "2") (pinfunction "2_2") (pintype "passive"))
      (node (ref "U13") (pin "6") (pinfunction "Vout_6") (pintype "passive"))
    )
    (net (code "41") (name "Net-(U15-+IN)") (class "Default")
      (node (ref "C56") (pin "2") (pinfunction "2_2") (pintype "passive"))
      (node (ref "R36") (pin "1") (pinfunction "1_1") (pintype "passive"))
      (node (ref "R38") (pin "2") (pinfunction "2_2") (pintype "passive"))
      (node (ref "U14") (pin "2") (pinfunction "2_2") (pintype "passive"))
      (node (ref "U15") (pin "3") (pinfunction "+IN_3") (pintype "passive"))
    )
    (net (code "42") (name "Net-(U15--IN)") (class "Default")
      (node (ref "C56") (pin "1") (pinfunction "1_1") (pintype "passive"))
      (node (ref "R32") (pin "2") (pinfunction "2_2") (pintype "passive"))
      (node (ref "R33") (pin "2") (pinfunction "2_2") (pintype "passive"))
      (node (ref "U15") (pin "2") (pinfunction "-IN_2") (pintype "passive"))
    )
    (net (code "43") (name "Net-(U15-Vout)") (class "Default")
      (node (ref "R37") (pin "2") (pinfunction "2_2") (pintype "passive"))
      (node (ref "U15") (pin "6") (pinfunction "Vout_6") (pintype "passive"))
    )
    (net (code "44") (name "VREFIN") (class "Default")
      (node (ref "R22") (pin "2") (pinfunction "2_2") (pintype "passive"))
      (node (ref "R23") (pin "2") (pinfunction "2_2") (pintype "passive"))
    )
  )
)
